# core.net
KiCad netlist of a schematic drawn in Altium Designer
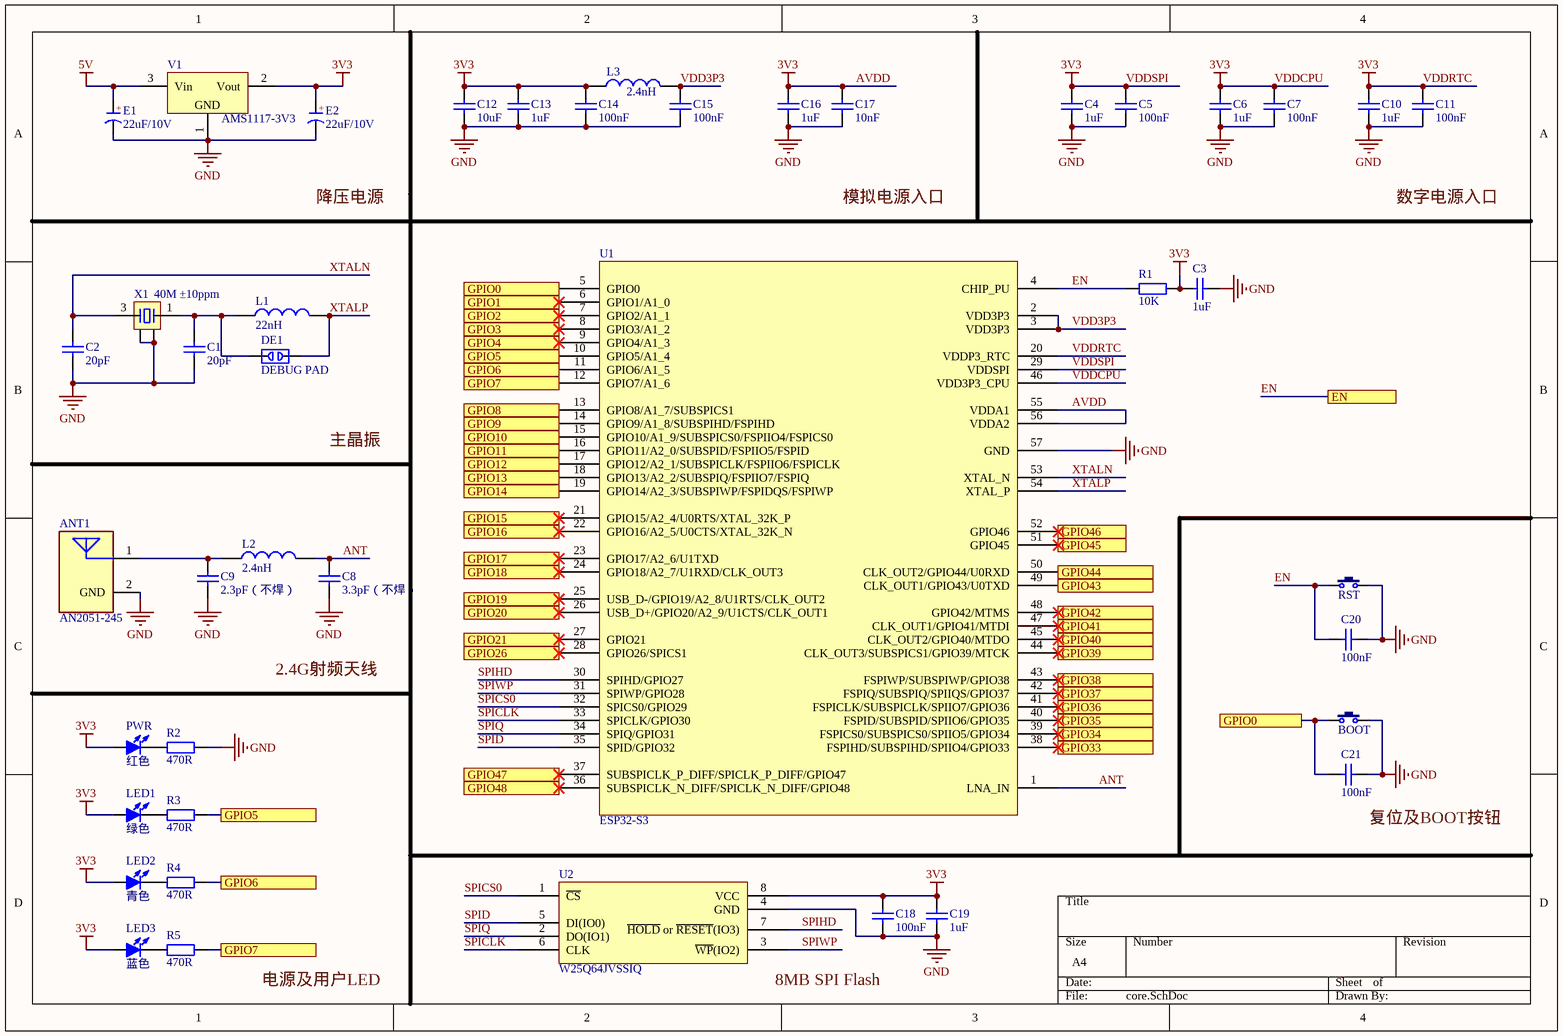
[diagram p0: core.SchDoc]

(export (version "E")
  (design (tool "Eeschema 10.0.6"))
  (components
    (comp (ref "ANT1")
      (value "AN2051-245")
      (footprint "SMD-2051")
      (description "AN2051 多层贴片天线 2.45GHz @110Mhz带宽 50ohm阻抗")
      (libsource (lib "1.8 - WiFi天线-SMA射频座") (part "AN2051"))
    )
    (comp (ref "BOOT")
      (value "3x6x5")
      (footprint "TSW SMD-3*6*2.5")
      (description "3x6轻触开关")
      (libsource (lib "0.7 - 常用按键-开关-蜂鸣器-电池") (part "TSW 3x6"))
    )
    (comp (ref "C1")
      (value "20pF")
      (footprint "C 0603_L")
      (description "贴片电容")
      (libsource (lib "0.1 - 电阻-电容-电感") (part "C"))
    )
    (comp (ref "C2")
      (value "20pF")
      (footprint "C 0603_L")
      (description "贴片电容")
      (libsource (lib "0.1 - 电阻-电容-电感") (part "C"))
    )
    (comp (ref "C3")
      (value "1uF")
      (footprint "C 0603_L")
      (description "贴片电容")
      (libsource (lib "0.1 - 电阻-电容-电感") (part "C"))
    )
    (comp (ref "C4")
      (value "1uF")
      (footprint "C 0603_L")
      (description "贴片电容")
      (libsource (lib "0.1 - 电阻-电容-电感") (part "C"))
    )
    (comp (ref "C5")
      (value "100nF")
      (footprint "C 0603_L")
      (description "贴片电容")
      (libsource (lib "0.1 - 电阻-电容-电感") (part "C"))
    )
    (comp (ref "C6")
      (value "1uF")
      (footprint "C 0603_L")
      (description "贴片电容")
      (libsource (lib "0.1 - 电阻-电容-电感") (part "C"))
    )
    (comp (ref "C7")
      (value "100nF")
      (footprint "C 0603_L")
      (description "贴片电容")
      (libsource (lib "0.1 - 电阻-电容-电感") (part "C"))
    )
    (comp (ref "C8")
      (value "3.3pF（不焊）")
      (footprint "C 0402_L")
      (description "精密电容")
      (libsource (lib "0.1 - 电阻-电容-电感") (part "C-Precision"))
    )
    (comp (ref "C9")
      (value "2.3pF（不焊）")
      (footprint "C 0402_L")
      (description "精密电容")
      (libsource (lib "0.1 - 电阻-电容-电感") (part "C-Precision"))
    )
    (comp (ref "C10")
      (value "1uF")
      (footprint "C 0603_L")
      (description "贴片电容")
      (libsource (lib "0.1 - 电阻-电容-电感") (part "C"))
    )
    (comp (ref "C11")
      (value "100nF")
      (footprint "C 0603_L")
      (description "贴片电容")
      (libsource (lib "0.1 - 电阻-电容-电感") (part "C"))
    )
    (comp (ref "C12")
      (value "10uF")
      (footprint "C 0603_L")
      (description "贴片电容")
      (libsource (lib "0.1 - 电阻-电容-电感") (part "C"))
    )
    (comp (ref "C13")
      (value "1uF")
      (footprint "C 0603_L")
      (description "贴片电容")
      (libsource (lib "0.1 - 电阻-电容-电感") (part "C"))
    )
    (comp (ref "C14")
      (value "100nF")
      (footprint "C 0603_L")
      (description "贴片电容")
      (libsource (lib "0.1 - 电阻-电容-电感") (part "C"))
    )
    (comp (ref "C15")
      (value "100nF")
      (footprint "C 0603_L")
      (description "贴片电容")
      (libsource (lib "0.1 - 电阻-电容-电感") (part "C"))
    )
    (comp (ref "C16")
      (value "1uF")
      (footprint "C 0603_L")
      (description "贴片电容")
      (libsource (lib "0.1 - 电阻-电容-电感") (part "C"))
    )
    (comp (ref "C17")
      (value "10nF")
      (footprint "C 0603_L")
      (description "贴片电容")
      (libsource (lib "0.1 - 电阻-电容-电感") (part "C"))
    )
    (comp (ref "C18")
      (value "100nF")
      (footprint "C 0603_L")
      (description "贴片电容")
      (libsource (lib "0.1 - 电阻-电容-电感") (part "C"))
    )
    (comp (ref "C19")
      (value "1uF")
      (footprint "C 0603_L")
      (description "贴片电容")
      (libsource (lib "0.1 - 电阻-电容-电感") (part "C"))
    )
    (comp (ref "C20")
      (value "100nF")
      (footprint "C 0603_L")
      (description "贴片电容")
      (libsource (lib "0.1 - 电阻-电容-电感") (part "C"))
    )
    (comp (ref "C21")
      (value "100nF")
      (footprint "C 0603_L")
      (description "贴片电容")
      (libsource (lib "0.1 - 电阻-电容-电感") (part "C"))
    )
    (comp (ref "DE1")
      (value "DEBUG PAD")
      (footprint "DEBUG_A")
      (description "调试断点焊盘")
      (libsource (lib "0.7 - 常用按键-开关-蜂鸣器-电池") (part "DEBUG"))
    )
    (comp (ref "E1")
      (value "22uF/10V")
      (footprint "CD A(3216)")
      (description "贴片钽电容")
      (libsource (lib "0.1 - 电阻-电容-电感") (part "CT"))
    )
    (comp (ref "E2")
      (value "22uF/10V")
      (footprint "CD A(3216)")
      (description "贴片钽电容")
      (libsource (lib "0.1 - 电阻-电容-电感") (part "CT"))
    )
    (comp (ref "L1")
      (value "22nH")
      (footprint "L 0603")
      (description "小功率贴片电感")
      (libsource (lib "0.1 - 电阻-电容-电感") (part "L"))
    )
    (comp (ref "L2")
      (value "2.4nH")
      (footprint "L 0402")
      (description "小功率贴片电感")
      (libsource (lib "0.1 - 电阻-电容-电感") (part "L"))
    )
    (comp (ref "L3")
      (value "2.4nH")
      (footprint "L 0402")
      (description "小功率贴片电感")
      (libsource (lib "") (part "L_1"))
    )
    (comp (ref "LED1")
      (value "绿色")
      (footprint "LED 0603B")
      (description "贴片LED")
      (libsource (lib "0.3 - LED发光二极管") (part "LED-SMD"))
    )
    (comp (ref "LED2")
      (value "青色")
      (footprint "LED 0603B")
      (description "贴片LED")
      (libsource (lib "0.3 - LED发光二极管") (part "LED-SMD"))
    )
    (comp (ref "LED3")
      (value "蓝色")
      (footprint "LED 0603B")
      (description "贴片LED")
      (libsource (lib "0.3 - LED发光二极管") (part "LED-SMD"))
    )
    (comp (ref "PWR")
      (value "红色")
      (footprint "LED 0603B")
      (description "贴片LED")
      (libsource (lib "0.3 - LED发光二极管") (part "LED-SMD"))
    )
    (comp (ref "R1")
      (value "10K")
      (footprint "R 0603_L")
      (description "贴片电阻")
      (libsource (lib "0.1 - 电阻-电容-电感") (part "R"))
    )
    (comp (ref "R2")
      (value "470R")
      (footprint "R 0603_L")
      (description "贴片电阻")
      (libsource (lib "0.1 - 电阻-电容-电感") (part "R"))
    )
    (comp (ref "R3")
      (value "470R")
      (footprint "R 0603_L")
      (description "贴片电阻")
      (libsource (lib "0.1 - 电阻-电容-电感") (part "R"))
    )
    (comp (ref "R4")
      (value "470R")
      (footprint "R 0603_L")
      (description "贴片电阻")
      (libsource (lib "0.1 - 电阻-电容-电感") (part "R"))
    )
    (comp (ref "R5")
      (value "470R")
      (footprint "R 0603_L")
      (description "贴片电阻")
      (libsource (lib "0.1 - 电阻-电容-电感") (part "R"))
    )
    (comp (ref "RST")
      (value "3x6x5")
      (footprint "TSW SMD-3*6*2.5")
      (description "3x6轻触开关")
      (libsource (lib "0.7 - 常用按键-开关-蜂鸣器-电池") (part "TSW 3x6"))
    )
    (comp (ref "U1")
      (value "ESP32-S3")
      (footprint "QFN56 7x7")
      (description "2.4 GHz Wi­Fi + 低功耗蓝牙 SoC")
      (libsource (lib "3.9 - ESP32系列芯片-模组") (part "ESP32-S3"))
    )
    (comp (ref "U2")
      (value "W25Q64JVSSIQ")
      (footprint "SOIC-8W")
      (description "8MB SPI Flash存储器")
      (libsource (lib "1.2 - 存储器-传感元件") (part "W25Q64"))
    )
    (comp (ref "V1")
      (value "AMS1117-3V3")
      (footprint "SOT223_L")
      (description "三端稳压芯片")
      (libsource (lib "1.0 - 电源类芯片") (part "AMS1117"))
    )
    (comp (ref "X1")
      (value "40M ±10ppm")
      (footprint "OSC 2025-4P")
      (description "4脚无源晶振")
      (fields (field (name "版权归属") "封装库来自淘宝卖家 ID：黄晶宝石"))
      (libsource (lib "0.5 - 保险丝-晶振-光耦") (part "XTAL-4P"))
    )
  )
  (nets
    (net (code "1") (name "/ANT") (class "Default")
      (node (ref "C8") (pin "2") (pinfunction "2_2") (pintype "passive"))
      (node (ref "L2") (pin "1") (pinfunction "1_1") (pintype "passive"))
      (node (ref "U1") (pin "1") (pinfunction "LNA_IN_1") (pintype "passive"))
    )
    (net (code "2") (name "/EN") (class "Default")
      (node (ref "C20") (pin "2") (pinfunction "2_2") (pintype "passive"))
      (node (ref "R1") (pin "1") (pinfunction "1_1") (pintype "passive"))
      (node (ref "RST") (pin "1") (pinfunction "1_1") (pintype "passive"))
      (node (ref "U1") (pin "4") (pinfunction "CHIP_PU_4") (pintype "passive"))
    )
    (net (code "3") (name "/GPIO0") (class "Default")
      (node (ref "BOOT") (pin "1") (pinfunction "1_1") (pintype "passive"))
      (node (ref "C21") (pin "2") (pinfunction "2_2") (pintype "passive"))
      (node (ref "U1") (pin "5") (pinfunction "GPIO0_5") (pintype "passive"))
    )
    (net (code "4") (name "/GPIO1") (class "Default")
      (node (ref "U1") (pin "6") (pinfunction "GPIO1/A1_0_6") (pintype "passive+no_connect"))
    )
    (net (code "5") (name "/GPIO2") (class "Default")
      (node (ref "U1") (pin "7") (pinfunction "GPIO2/A1_1_7") (pintype "passive+no_connect"))
    )
    (net (code "6") (name "/GPIO3") (class "Default")
      (node (ref "U1") (pin "8") (pinfunction "GPIO3/A1_2_8") (pintype "passive+no_connect"))
    )
    (net (code "7") (name "/GPIO4") (class "Default")
      (node (ref "U1") (pin "9") (pinfunction "GPIO4/A1_3_9") (pintype "passive+no_connect"))
    )
    (net (code "8") (name "/GPIO5") (class "Default")
      (node (ref "R3") (pin "2") (pinfunction "2_2") (pintype "passive"))
      (node (ref "U1") (pin "10") (pinfunction "GPIO5/A1_4_10") (pintype "passive"))
    )
    (net (code "9") (name "/GPIO6") (class "Default")
      (node (ref "R4") (pin "2") (pinfunction "2_2") (pintype "passive"))
      (node (ref "U1") (pin "11") (pinfunction "GPIO6/A1_5_11") (pintype "passive"))
    )
    (net (code "10") (name "/GPIO7") (class "Default")
      (node (ref "R5") (pin "2") (pinfunction "2_2") (pintype "passive"))
      (node (ref "U1") (pin "12") (pinfunction "GPIO7/A1_6_12") (pintype "passive"))
    )
    (net (code "11") (name "/GPIO8") (class "Default")
      (node (ref "U1") (pin "13") (pinfunction "GPIO8/A1_7/SUBSPICS1_13") (pintype "passive"))
    )
    (net (code "12") (name "/GPIO9") (class "Default")
      (node (ref "U1") (pin "14") (pinfunction "GPIO9/A1_8/SUBSPIHD/FSPIHD_14") (pintype "passive"))
    )
    (net (code "13") (name "/GPIO10") (class "Default")
      (node (ref "U1") (pin "15") (pinfunction "GPIO10/A1_9/SUBSPICS0/FSPIIO4/FSPICS0_15") (pintype "passive"))
    )
    (net (code "14") (name "/GPIO11") (class "Default")
      (node (ref "U1") (pin "16") (pinfunction "GPIO11/A2_0/SUBSPID/FSPIIO5/FSPID_16") (pintype "passive"))
    )
    (net (code "15") (name "/GPIO12") (class "Default")
      (node (ref "U1") (pin "17") (pinfunction "GPIO12/A2_1/SUBSPICLK/FSPIIO6/FSPICLK_17") (pintype "passive"))
    )
    (net (code "16") (name "/GPIO13") (class "Default")
      (node (ref "U1") (pin "18") (pinfunction "GPIO13/A2_2/SUBSPIQ/FSPIIO7/FSPIQ_18") (pintype "passive"))
    )
    (net (code "17") (name "/GPIO14") (class "Default")
      (node (ref "U1") (pin "19") (pinfunction "GPIO14/A2_3/SUBSPIWP/FSPIDQS/FSPIWP_19") (pintype "passive"))
    )
    (net (code "18") (name "/GPIO15") (class "Default")
      (node (ref "U1") (pin "21") (pinfunction "GPIO15/A2_4/U0RTS/XTAL_32K_P_21") (pintype "passive+no_connect"))
    )
    (net (code "19") (name "/GPIO16") (class "Default")
      (node (ref "U1") (pin "22") (pinfunction "GPIO16/A2_5/U0CTS/XTAL_32K_N_22") (pintype "passive+no_connect"))
    )
    (net (code "20") (name "/GPIO17") (class "Default")
      (node (ref "U1") (pin "23") (pinfunction "GPIO17/A2_6/U1TXD_23") (pintype "passive+no_connect"))
    )
    (net (code "21") (name "/GPIO18") (class "Default")
      (node (ref "U1") (pin "24") (pinfunction "GPIO18/A2_7/U1RXD/CLK_OUT3_24") (pintype "passive+no_connect"))
    )
    (net (code "22") (name "/GPIO19") (class "Default")
      (node (ref "U1") (pin "25") (pinfunction "USB_D-/GPIO19/A2_8/U1RTS/CLK_OUT2_25") (pintype "passive+no_connect"))
    )
    (net (code "23") (name "/GPIO20") (class "Default")
      (node (ref "U1") (pin "26") (pinfunction "USB_D+/GPIO20/A2_9/U1CTS/CLK_OUT1_26") (pintype "passive+no_connect"))
    )
    (net (code "24") (name "/GPIO21") (class "Default")
      (node (ref "U1") (pin "27") (pinfunction "GPIO21_27") (pintype "passive+no_connect"))
    )
    (net (code "25") (name "/GPIO26") (class "Default")
      (node (ref "U1") (pin "28") (pinfunction "GPIO26/SPICS1_28") (pintype "passive+no_connect"))
    )
    (net (code "26") (name "/GPIO33") (class "Default")
      (node (ref "U1") (pin "38") (pinfunction "FSPIHD/SUBSPIHD/SPIIO4/GPIO33_38") (pintype "passive+no_connect"))
    )
    (net (code "27") (name "/GPIO34") (class "Default")
      (node (ref "U1") (pin "39") (pinfunction "FSPICS0/SUBSPICS0/SPIIO5/GPIO34_39") (pintype "passive+no_connect"))
    )
    (net (code "28") (name "/GPIO35") (class "Default")
      (node (ref "U1") (pin "40") (pinfunction "FSPID/SUBSPID/SPIIO6/GPIO35_40") (pintype "passive+no_connect"))
    )
    (net (code "29") (name "/GPIO36") (class "Default")
      (node (ref "U1") (pin "41") (pinfunction "FSPICLK/SUBSPICLK/SPIIO7/GPIO36_41") (pintype "passive+no_connect"))
    )
    (net (code "30") (name "/GPIO37") (class "Default")
      (node (ref "U1") (pin "42") (pinfunction "FSPIQ/SUBSPIQ/SPIIQS/GPIO37_42") (pintype "passive+no_connect"))
    )
    (net (code "31") (name "/GPIO38") (class "Default")
      (node (ref "U1") (pin "43") (pinfunction "FSPIWP/SUBSPIWP/GPIO38_43") (pintype "passive+no_connect"))
    )
    (net (code "32") (name "/GPIO39") (class "Default")
      (node (ref "U1") (pin "44") (pinfunction "CLK_OUT3/SUBSPICS1/GPIO39/MTCK_44") (pintype "passive+no_connect"))
    )
    (net (code "33") (name "/GPIO40") (class "Default")
      (node (ref "U1") (pin "45") (pinfunction "CLK_OUT2/GPIO40/MTDO_45") (pintype "passive+no_connect"))
    )
    (net (code "34") (name "/GPIO41") (class "Default")
      (node (ref "U1") (pin "47") (pinfunction "CLK_OUT1/GPIO41/MTDI_47") (pintype "passive+no_connect"))
    )
    (net (code "35") (name "/GPIO42") (class "Default")
      (node (ref "U1") (pin "48") (pinfunction "GPIO42/MTMS_48") (pintype "passive+no_connect"))
    )
    (net (code "36") (name "/GPIO43") (class "Default")
      (node (ref "U1") (pin "49") (pinfunction "CLK_OUT1/GPIO43/U0TXD_49") (pintype "passive"))
    )
    (net (code "37") (name "/GPIO44") (class "Default")
      (node (ref "U1") (pin "50") (pinfunction "CLK_OUT2/GPIO44/U0RXD_50") (pintype "passive"))
    )
    (net (code "38") (name "/GPIO45") (class "Default")
      (node (ref "U1") (pin "51") (pinfunction "GPIO45_51") (pintype "passive+no_connect"))
    )
    (net (code "39") (name "/GPIO46") (class "Default")
      (node (ref "U1") (pin "52") (pinfunction "GPIO46_52") (pintype "passive+no_connect"))
    )
    (net (code "40") (name "/GPIO47") (class "Default")
      (node (ref "U1") (pin "37") (pinfunction "SUBSPICLK_P_DIFF/SPICLK_P_DIFF/GPIO47_37") (pintype "passive+no_connect"))
    )
    (net (code "41") (name "/GPIO48") (class "Default")
      (node (ref "U1") (pin "36") (pinfunction "SUBSPICLK_N_DIFF/SPICLK_N_DIFF/GPIO48_36") (pintype "passive+no_connect"))
    )
    (net (code "42") (name "/SPICLK") (class "Default")
      (node (ref "U1") (pin "33") (pinfunction "SPICLK/GPIO30_33") (pintype "passive"))
      (node (ref "U2") (pin "6") (pinfunction "CLK_6") (pintype "passive"))
    )
    (net (code "43") (name "/SPICS0") (class "Default")
      (node (ref "U1") (pin "32") (pinfunction "SPICS0/GPIO29_32") (pintype "passive"))
      (node (ref "U2") (pin "1") (pinfunction "~{CS}_1") (pintype "passive"))
    )
    (net (code "44") (name "/SPID") (class "Default")
      (node (ref "U1") (pin "35") (pinfunction "SPID/GPIO32_35") (pintype "passive"))
      (node (ref "U2") (pin "5") (pinfunction "DI(IO0)_5") (pintype "passive"))
    )
    (net (code "45") (name "/SPIHD") (class "Default")
      (node (ref "U1") (pin "30") (pinfunction "SPIHD/GPIO27_30") (pintype "passive"))
      (node (ref "U2") (pin "7") (pinfunction "~{HOLD}_or_~{RESET}(IO3)_7") (pintype "passive"))
    )
    (net (code "46") (name "/SPIQ") (class "Default")
      (node (ref "U1") (pin "34") (pinfunction "SPIQ/GPIO31_34") (pintype "passive"))
      (node (ref "U2") (pin "2") (pinfunction "DO(IO1)_2") (pintype "passive"))
    )
    (net (code "47") (name "/SPIWP") (class "Default")
      (node (ref "U1") (pin "31") (pinfunction "SPIWP/GPIO28_31") (pintype "passive"))
      (node (ref "U2") (pin "3") (pinfunction "~{WP}(IO2)_3") (pintype "passive"))
    )
    (net (code "48") (name "/VDD3P3") (class "Default")
      (node (ref "C15") (pin "1") (pinfunction "1_1") (pintype "passive"))
      (node (ref "L3") (pin "2") (pinfunction "2_2") (pintype "passive"))
      (node (ref "U1") (pin "2") (pinfunction "VDD3P3_2") (pintype "passive"))
      (node (ref "U1") (pin "3") (pinfunction "VDD3P3_3") (pintype "passive"))
    )
    (net (code "49") (name "/XTALN") (class "Default")
      (node (ref "C2") (pin "2") (pinfunction "2_2") (pintype "passive"))
      (node (ref "U1") (pin "53") (pinfunction "XTAL_N_53") (pintype "passive"))
      (node (ref "X1") (pin "3") (pinfunction "3_3") (pintype "passive"))
    )
    (net (code "50") (name "/XTALP") (class "Default")
      (node (ref "DE1") (pin "1") (pinfunction "1_1") (pintype "passive"))
      (node (ref "L1") (pin "1") (pinfunction "1_1") (pintype "passive"))
      (node (ref "U1") (pin "54") (pinfunction "XTAL_P_54") (pintype "passive"))
    )
    (net (code "51") (name "3V3") (class "Default")
      (node (ref "C10") (pin "1") (pinfunction "1_1") (pintype "passive"))
      (node (ref "C11") (pin "1") (pinfunction "1_1") (pintype "passive"))
      (node (ref "C12") (pin "1") (pinfunction "1_1") (pintype "passive"))
      (node (ref "C13") (pin "1") (pinfunction "1_1") (pintype "passive"))
      (node (ref "C14") (pin "1") (pinfunction "1_1") (pintype "passive"))
      (node (ref "C16") (pin "1") (pinfunction "1_1") (pintype "passive"))
      (node (ref "C17") (pin "1") (pinfunction "1_1") (pintype "passive"))
      (node (ref "C18") (pin "1") (pinfunction "1_1") (pintype "passive"))
      (node (ref "C19") (pin "1") (pinfunction "1_1") (pintype "passive"))
      (node (ref "C3") (pin "2") (pinfunction "2_2") (pintype "passive"))
      (node (ref "C4") (pin "1") (pinfunction "1_1") (pintype "passive"))
      (node (ref "C5") (pin "1") (pinfunction "1_1") (pintype "passive"))
      (node (ref "C6") (pin "1") (pinfunction "1_1") (pintype "passive"))
      (node (ref "C7") (pin "1") (pinfunction "1_1") (pintype "passive"))
      (node (ref "E2") (pin "1") (pinfunction "A_1") (pintype "passive"))
      (node (ref "L3") (pin "1") (pinfunction "1_1") (pintype "passive"))
      (node (ref "LED1") (pin "1") (pinfunction "A_1") (pintype "passive"))
      (node (ref "LED2") (pin "1") (pinfunction "A_1") (pintype "passive"))
      (node (ref "LED3") (pin "1") (pinfunction "A_1") (pintype "passive"))
      (node (ref "PWR") (pin "1") (pinfunction "A_1") (pintype "passive"))
      (node (ref "R1") (pin "2") (pinfunction "2_2") (pintype "passive"))
      (node (ref "U1") (pin "20") (pinfunction "VDDP3_RTC_20") (pintype "passive"))
      (node (ref "U1") (pin "29") (pinfunction "VDDSPI_29") (pintype "passive"))
      (node (ref "U1") (pin "46") (pinfunction "VDD3P3_CPU_46") (pintype "passive"))
      (node (ref "U1") (pin "55") (pinfunction "VDDA1_55") (pintype "passive"))
      (node (ref "U1") (pin "56") (pinfunction "VDDA2_56") (pintype "passive"))
      (node (ref "U2") (pin "8") (pinfunction "VCC_8") (pintype "passive"))
      (node (ref "V1") (pin "2") (pinfunction "Vout_2") (pintype "passive"))
    )
    (net (code "52") (name "5V") (class "Default")
      (node (ref "E1") (pin "1") (pinfunction "A_1") (pintype "passive"))
      (node (ref "V1") (pin "3") (pinfunction "Vin_3") (pintype "passive"))
    )
    (net (code "53") (name "GND") (class "Default")
      (node (ref "ANT1") (pin "2") (pinfunction "GND_2") (pintype "passive"))
      (node (ref "BOOT") (pin "2") (pinfunction "2_2") (pintype "passive"))
      (node (ref "C1") (pin "1") (pinfunction "1_1") (pintype "passive"))
      (node (ref "C10") (pin "2") (pinfunction "2_2") (pintype "passive"))
      (node (ref "C11") (pin "2") (pinfunction "2_2") (pintype "passive"))
      (node (ref "C12") (pin "2") (pinfunction "2_2") (pintype "passive"))
      (node (ref "C13") (pin "2") (pinfunction "2_2") (pintype "passive"))
      (node (ref "C14") (pin "2") (pinfunction "2_2") (pintype "passive"))
      (node (ref "C15") (pin "2") (pinfunction "2_2") (pintype "passive"))
      (node (ref "C16") (pin "2") (pinfunction "2_2") (pintype "passive"))
      (node (ref "C17") (pin "2") (pinfunction "2_2") (pintype "passive"))
      (node (ref "C18") (pin "2") (pinfunction "2_2") (pintype "passive"))
      (node (ref "C19") (pin "2") (pinfunction "2_2") (pintype "passive"))
      (node (ref "C2") (pin "1") (pinfunction "1_1") (pintype "passive"))
      (node (ref "C20") (pin "1") (pinfunction "1_1") (pintype "passive"))
      (node (ref "C21") (pin "1") (pinfunction "1_1") (pintype "passive"))
      (node (ref "C3") (pin "1") (pinfunction "1_1") (pintype "passive"))
      (node (ref "C4") (pin "2") (pinfunction "2_2") (pintype "passive"))
      (node (ref "C5") (pin "2") (pinfunction "2_2") (pintype "passive"))
      (node (ref "C6") (pin "2") (pinfunction "2_2") (pintype "passive"))
      (node (ref "C7") (pin "2") (pinfunction "2_2") (pintype "passive"))
      (node (ref "C8") (pin "1") (pinfunction "1_1") (pintype "passive"))
      (node (ref "C9") (pin "1") (pinfunction "1_1") (pintype "passive"))
      (node (ref "E1") (pin "2") (pinfunction "K_2") (pintype "passive"))
      (node (ref "E2") (pin "2") (pinfunction "K_2") (pintype "passive"))
      (node (ref "R2") (pin "2") (pinfunction "2_2") (pintype "passive"))
      (node (ref "RST") (pin "2") (pinfunction "2_2") (pintype "passive"))
      (node (ref "U1") (pin "57") (pinfunction "GND_57") (pintype "passive"))
      (node (ref "U2") (pin "4") (pinfunction "GND_4") (pintype "passive"))
      (node (ref "V1") (pin "1") (pinfunction "GND_1") (pintype "passive"))
      (node (ref "X1") (pin "2") (pinfunction "2_2") (pintype "passive"))
      (node (ref "X1") (pin "4") (pinfunction "4_4") (pintype "passive"))
    )
    (net (code "54") (name "Net-(ANT1-FT)") (class "Default")
      (node (ref "ANT1") (pin "1") (pinfunction "FT_1") (pintype "passive"))
      (node (ref "C9") (pin "2") (pinfunction "2_2") (pintype "passive"))
      (node (ref "L2") (pin "2") (pinfunction "2_2") (pintype "passive"))
    )
    (net (code "55") (name "Net-(C1-Pad2)") (class "Default")
      (node (ref "C1") (pin "2") (pinfunction "2_2") (pintype "passive"))
      (node (ref "DE1") (pin "2") (pinfunction "2_2") (pintype "passive"))
      (node (ref "L1") (pin "2") (pinfunction "2_2") (pintype "passive"))
      (node (ref "X1") (pin "1") (pinfunction "1_1") (pintype "passive"))
    )
    (net (code "56") (name "Net-(LED1-K)") (class "Default")
      (node (ref "LED1") (pin "2") (pinfunction "K_2") (pintype "passive"))
      (node (ref "R3") (pin "1") (pinfunction "1_1") (pintype "passive"))
    )
    (net (code "57") (name "Net-(LED2-K)") (class "Default")
      (node (ref "LED2") (pin "2") (pinfunction "K_2") (pintype "passive"))
      (node (ref "R4") (pin "1") (pinfunction "1_1") (pintype "passive"))
    )
    (net (code "58") (name "Net-(LED3-K)") (class "Default")
      (node (ref "LED3") (pin "2") (pinfunction "K_2") (pintype "passive"))
      (node (ref "R5") (pin "1") (pinfunction "1_1") (pintype "passive"))
    )
    (net (code "59") (name "Net-(PWR-K)") (class "Default")
      (node (ref "PWR") (pin "2") (pinfunction "K_2") (pintype "passive"))
      (node (ref "R2") (pin "1") (pinfunction "1_1") (pintype "passive"))
    )
  )
)
